# Sheet2.net
KiCad netlist of a schematic drawn in Altium Designer
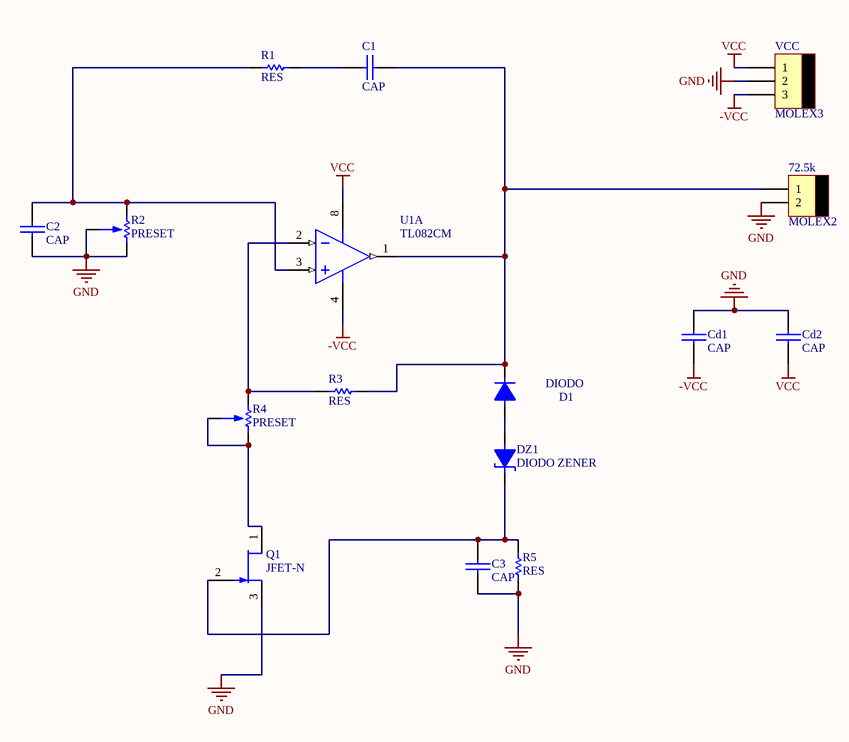
[diagram p0: Sheet2.SchDoc]

(export (version "E")
  (design (tool "Eeschema 10.0.6"))
  (components
    (comp (ref "72.5k") (value "MOLEX2") (footprint "MOLEX2") (libsource (lib "LIB PIO IX") (part "MOLEX2")))
    (comp (ref "C1") (value "CAP") (footprint "0805") (libsource (lib "LIB PIO IX") (part "CAP")))
    (comp (ref "C2") (value "CAP") (footprint "0805") (libsource (lib "LIB PIO IX") (part "CAP")))
    (comp (ref "C3") (value "CAP") (footprint "0805") (libsource (lib "LIB PIO IX") (part "CAP")))
    (comp (ref "Cd1") (value "CAP") (footprint "0805") (libsource (lib "LIB PIO IX") (part "CAP")))
    (comp (ref "Cd2") (value "CAP") (footprint "0805") (libsource (lib "LIB PIO IX") (part "CAP")))
    (comp (ref "D1") (value "DIODO") (footprint "DO41") (libsource (lib "LIB PIO IX") (part "DIODO")))
    (comp (ref "DZ1")
      (value "DIODO ZENER")
      (footprint "DO41")
      (libsource (lib "LIB PIO IX") (part "DIODO ZENER"))
    )
    (comp (ref "Q1")
      (value "JFET-N")
      (footprint "TO-254-AA")
      (description "N-Channel JFET")
      (fields (field (name "PUBLISHER") "Altium Limited"))
      (libsource (lib "Miscellaneous Devices") (part "JFET-N"))
    )
    (comp (ref "R1") (value "RES") (footprint "0805") (libsource (lib "LIB PIO IX") (part "RES")))
    (comp (ref "R2") (value "PRESET") (footprint "PRESET V") (libsource (lib "LIBEBAL") (part "PRESET")))
    (comp (ref "R3") (value "RES") (footprint "0805") (libsource (lib "LIB PIO IX") (part "RES")))
    (comp (ref "R4") (value "PRESET") (footprint "PRESET V") (libsource (lib "LIBEBAL") (part "PRESET")))
    (comp (ref "R5") (value "RES") (footprint "0805") (libsource (lib "LIB PIO IX") (part "RES")))
    (comp (ref "U1")
      (value "TL082CM")
      (footprint "M08A_N")
      (description "Wide Bandwidth Dual JFET Input Operational Amplifier, 8-pin Narrow SOIC")
      (fields
        (field (name "MANUFACTURER") "National Semiconductor")
        (field (name "PUBLISHER") "Altium Limited")
      )
      (libsource (lib "NSC Amplifier") (part "TL082CM"))
    )
    (comp (ref "VCC") (value "MOLEX3") (footprint "MOLEX3") (libsource (lib "LIB PIO IX") (part "MOLEX3")))
  )
  (nets
    (net (code "1") (name "-VCC") (class "Default")
      (node (ref "Cd1") (pin "2") (pinfunction "2_2") (pintype "passive"))
      (node (ref "U1") (pin "4") (pinfunction "V-_4") (pintype "power_in"))
      (node (ref "VCC") (pin "3") (pinfunction "3_3") (pintype "passive"))
    )
    (net (code "2") (name "GND") (class "Default")
      (node (ref "72.5k") (pin "2") (pinfunction "2_2") (pintype "passive"))
      (node (ref "C2") (pin "2") (pinfunction "2_2") (pintype "passive"))
      (node (ref "C3") (pin "1") (pinfunction "1_1") (pintype "passive"))
      (node (ref "Cd1") (pin "1") (pinfunction "1_1") (pintype "passive"))
      (node (ref "Cd2") (pin "1") (pinfunction "1_1") (pintype "passive"))
      (node (ref "Q1") (pin "3") (pinfunction "S_3") (pintype "passive"))
      (node (ref "R2") (pin "1") (pinfunction "1_1") (pintype "passive"))
      (node (ref "R2") (pin "2") (pinfunction "2_2") (pintype "passive"))
      (node (ref "R5") (pin "1") (pinfunction "1_1") (pintype "passive"))
      (node (ref "VCC") (pin "2") (pinfunction "2_2") (pintype "passive"))
    )
    (net (code "3") (name "Net-(C1-Pad1)") (class "Default")
      (node (ref "C1") (pin "1") (pinfunction "1_1") (pintype "passive"))
      (node (ref "R1") (pin "1") (pinfunction "1_1") (pintype "passive"))
    )
    (net (code "4") (name "Net-(D1-Pad1)") (class "Default")
      (node (ref "D1") (pin "1") (pinfunction "1_1") (pintype "passive"))
      (node (ref "DZ1") (pin "1") (pinfunction "1_1") (pintype "passive"))
    )
    (net (code "5") (name "Net-(Q1-D)") (class "Default")
      (node (ref "Q1") (pin "1") (pinfunction "D_1") (pintype "passive"))
      (node (ref "R4") (pin "1") (pinfunction "1_1") (pintype "passive"))
      (node (ref "R4") (pin "2") (pinfunction "2_2") (pintype "passive"))
    )
    (net (code "6") (name "Net-(Q1-G)") (class "Default")
      (node (ref "C3") (pin "2") (pinfunction "2_2") (pintype "passive"))
      (node (ref "DZ1") (pin "2") (pinfunction "2_2") (pintype "passive"))
      (node (ref "Q1") (pin "2") (pinfunction "G_2") (pintype "passive"))
      (node (ref "R5") (pin "2") (pinfunction "2_2") (pintype "passive"))
    )
    (net (code "7") (name "Net-(U1A-INA+)") (class "Default")
      (node (ref "C2") (pin "1") (pinfunction "1_1") (pintype "passive"))
      (node (ref "R1") (pin "2") (pinfunction "2_2") (pintype "passive"))
      (node (ref "R2") (pin "3") (pinfunction "3_3") (pintype "passive"))
      (node (ref "U1") (pin "3") (pinfunction "INA+_3") (pintype "input"))
    )
    (net (code "8") (name "Net-(U1A-INA-)") (class "Default")
      (node (ref "R3") (pin "1") (pinfunction "1_1") (pintype "passive"))
      (node (ref "R4") (pin "3") (pinfunction "3_3") (pintype "passive"))
      (node (ref "U1") (pin "2") (pinfunction "INA-_2") (pintype "input"))
    )
    (net (code "9") (name "Net-(U1A-OUTA)") (class "Default")
      (node (ref "72.5k") (pin "1") (pinfunction "1_1") (pintype "passive"))
      (node (ref "C1") (pin "2") (pinfunction "2_2") (pintype "passive"))
      (node (ref "D1") (pin "2") (pinfunction "2_2") (pintype "passive"))
      (node (ref "R3") (pin "2") (pinfunction "2_2") (pintype "passive"))
      (node (ref "U1") (pin "1") (pinfunction "OUTA_1") (pintype "output"))
    )
    (net (code "10") (name "VCC") (class "Default")
      (node (ref "Cd2") (pin "2") (pinfunction "2_2") (pintype "passive"))
      (node (ref "U1") (pin "8") (pinfunction "V+_8") (pintype "power_in"))
      (node (ref "VCC") (pin "1") (pinfunction "1_1") (pintype "passive"))
    )
  )
)
